# Qwiic_RTC_RV8803.net
KiCad netlist of a schematic drawn in EAGLE
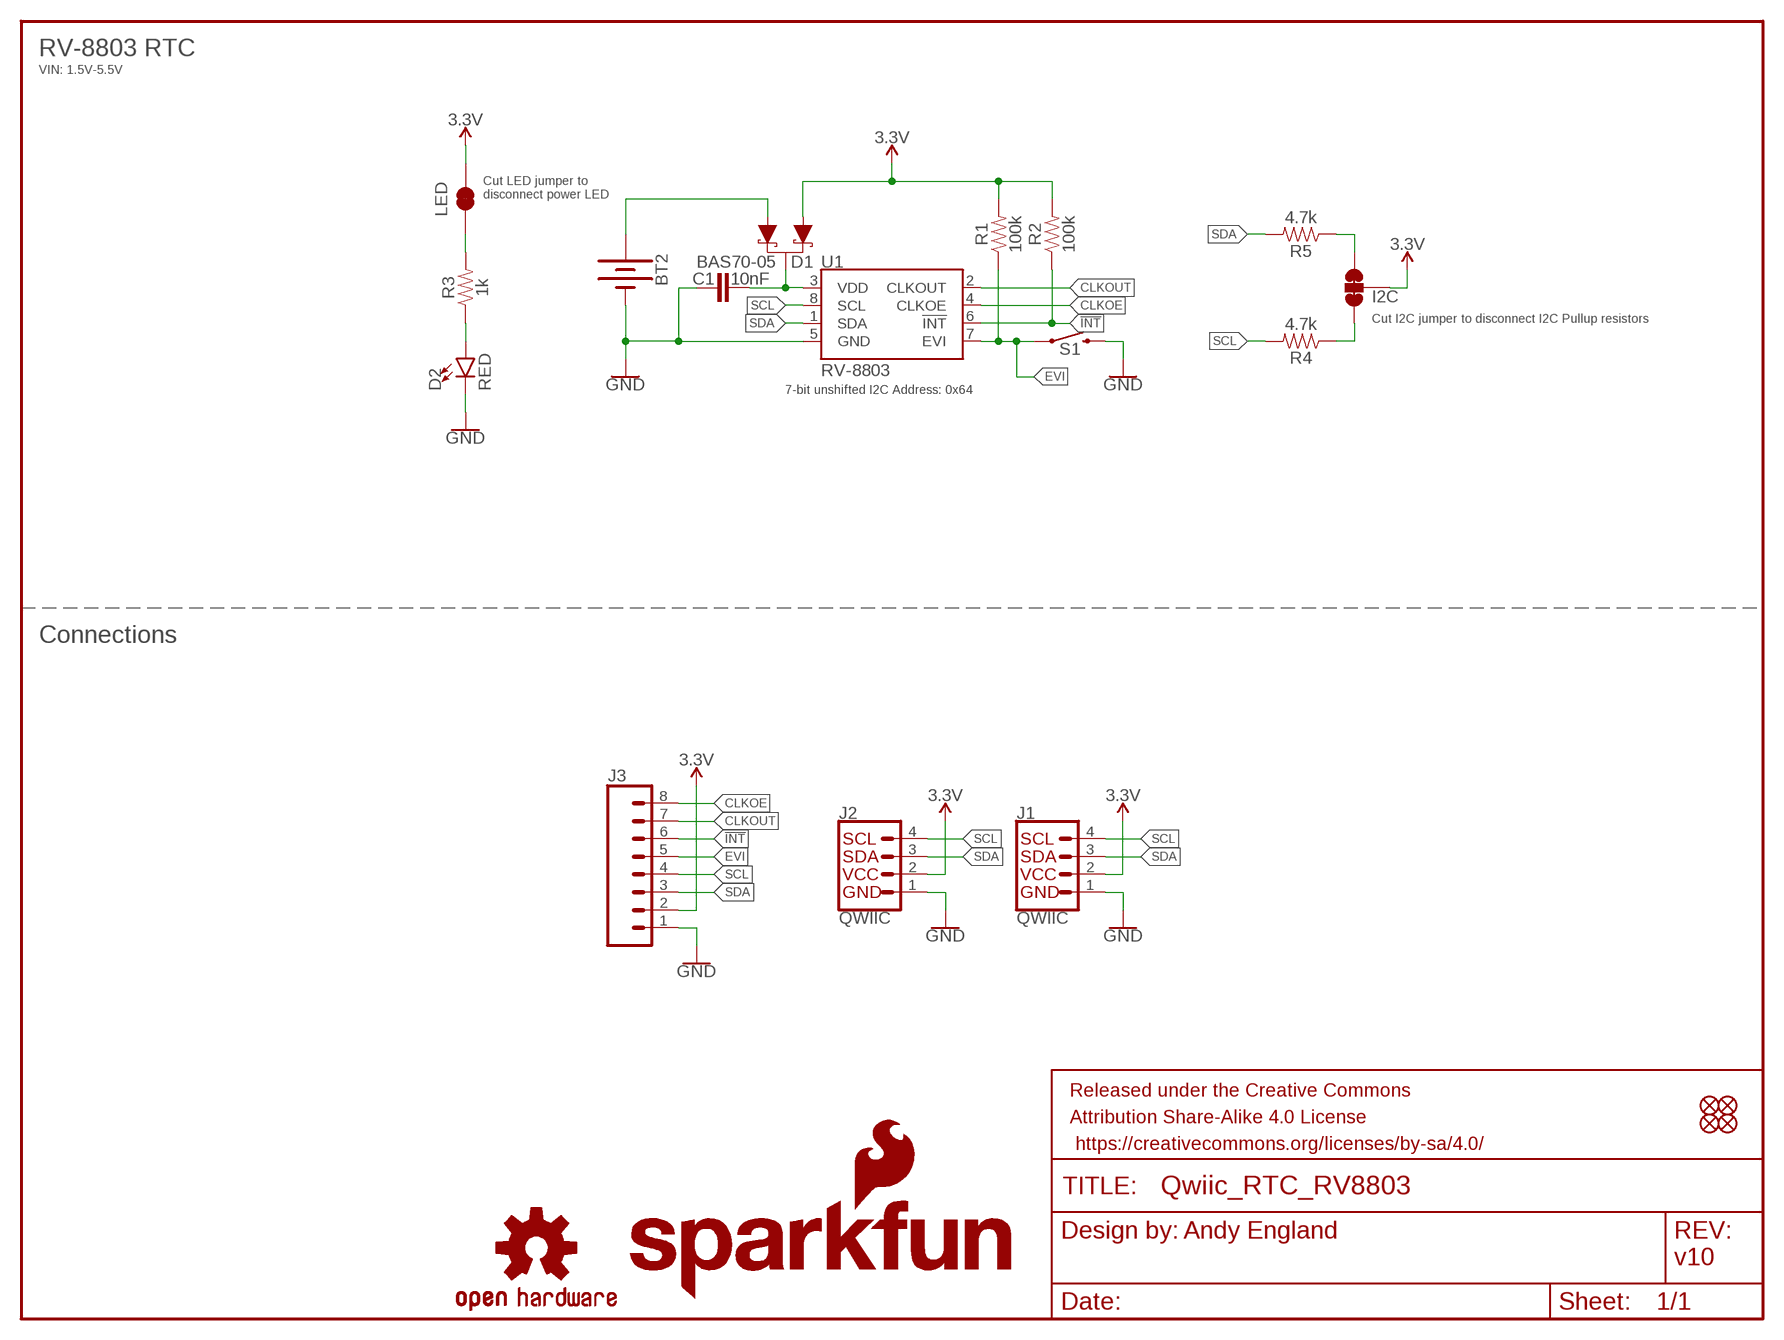
[diagram p0: schematic, sheet 1]

(export (version "E")
  (design (tool "Eeschema 10.0.6"))
  (components
    (comp (ref "BT2")
      (value "BATTERY-12MM_SMD")
      (footprint "eagle-import:BATTCON_12MM")
      (libsource (lib "eagle-import") (part "BATTERY-12MM_SMD"))
    )
    (comp (ref "C1")
      (value "10nF")
      (footprint "eagle-import:0603")
      (libsource (lib "eagle-import") (part "10NF-0603-50V-10%"))
    )
    (comp (ref "D1")
      (value "BAS70-05")
      (footprint "eagle-import:SOT23-3")
      (libsource (lib "eagle-import") (part "DIODE-SCHOTTKY-DUAL"))
    )
    (comp (ref "D2")
      (value "RED")
      (footprint "eagle-import:LED-0603")
      (libsource (lib "eagle-import") (part "LED-RED0603"))
    )
    (comp (ref "FD1")
      (value "FIDUCIALUFIDUCIAL")
      (footprint "eagle-import:FIDUCIAL-MICRO")
      (libsource (lib "eagle-import") (part "FIDUCIALUFIDUCIAL"))
    )
    (comp (ref "FD2")
      (value "FIDUCIALUFIDUCIAL")
      (footprint "eagle-import:FIDUCIAL-MICRO")
      (libsource (lib "eagle-import") (part "FIDUCIALUFIDUCIAL"))
    )
    (comp (ref "FD3")
      (value "FIDUCIALUFIDUCIAL")
      (footprint "eagle-import:FIDUCIAL-MICRO")
      (libsource (lib "eagle-import") (part "FIDUCIALUFIDUCIAL"))
    )
    (comp (ref "FD4")
      (value "FIDUCIALUFIDUCIAL")
      (footprint "eagle-import:FIDUCIAL-MICRO")
      (libsource (lib "eagle-import") (part "FIDUCIALUFIDUCIAL"))
    )
    (comp (ref "FRAME1")
      (value "FRAME-LETTER")
      (footprint "eagle-import:CREATIVE_COMMONS")
      (libsource (lib "eagle-import") (part "FRAME-LETTER"))
    )
    (comp (ref "I2C")
      (value "JUMPER-SMT_3_2-NC_TRACE_NO-SILK")
      (footprint "eagle-import:SMT-JUMPER_3_2-NC_TRACE_NO-SILK")
      (libsource (lib "eagle-import") (part "JUMPER-SMT_3_2-NC_TRACE_NO-SILK"))
    )
    (comp (ref "J1")
      (value "QWIIC")
      (footprint "eagle-import:JST04_1MM_RA")
      (libsource (lib "eagle-import") (part "QWIIC_CONNECTORJS-1MM"))
    )
    (comp (ref "J2")
      (value "QWIIC")
      (footprint "eagle-import:JST04_1MM_RA")
      (libsource (lib "eagle-import") (part "QWIIC_CONNECTORJS-1MM"))
    )
    (comp (ref "J3")
      (value "CONN_08NO_SILK_FEMALE_PTH")
      (footprint "eagle-import:1X08_NO_SILK")
      (libsource (lib "eagle-import") (part "CONN_08NO_SILK_FEMALE_PTH"))
    )
    (comp (ref "LED")
      (value "JUMPER-SMT_2_NC_TRACE_NO-SILK")
      (footprint "eagle-import:SMT-JUMPER_2_NC_TRACE_NO-SILK")
      (libsource (lib "eagle-import") (part "JUMPER-SMT_2_NC_TRACE_NO-SILK"))
    )
    (comp (ref "LOGO1")
      (value "SFE_LOGO_NAME_FLAME.1_INCH")
      (footprint "eagle-import:SFE_LOGO_NAME_FLAME_.1")
      (libsource (lib "eagle-import") (part "SFE_LOGO_NAME_FLAME.1_INCH"))
    )
    (comp (ref "LOGO2")
      (value "OSHW-LOGOS")
      (footprint "eagle-import:OSHW-LOGO-S")
      (libsource (lib "eagle-import") (part "OSHW-LOGOS"))
    )
    (comp (ref "LOGO3")
      (value "SFE_LOGO_FLAME.1_INCH")
      (footprint "eagle-import:SFE_LOGO_FLAME_.1")
      (libsource (lib "eagle-import") (part "SFE_LOGO_FLAME.1_INCH"))
    )
    (comp (ref "R1")
      (value "100k")
      (footprint "eagle-import:0603")
      (libsource (lib "eagle-import") (part "100KOHM-0603-1/10W-1%"))
    )
    (comp (ref "R2")
      (value "100k")
      (footprint "eagle-import:0603")
      (libsource (lib "eagle-import") (part "100KOHM-0603-1/10W-1%"))
    )
    (comp (ref "R3")
      (value "1k")
      (footprint "eagle-import:0603")
      (libsource (lib "eagle-import") (part "1KOHM-0603-1/10W-1%"))
    )
    (comp (ref "R4")
      (value "4.7k")
      (footprint "eagle-import:0603")
      (libsource (lib "eagle-import") (part "4.7KOHM-0603-1/10W-1%"))
    )
    (comp (ref "R5")
      (value "4.7k")
      (footprint "eagle-import:0603")
      (libsource (lib "eagle-import") (part "4.7KOHM-0603-1/10W-1%"))
    )
    (comp (ref "S1")
      (value "MOMENTARY-SWITCH-SPST-SMD-4.6X2.8MM")
      (footprint "eagle-import:TACTILE_SWITCH_SMD_4.6X2.8MM")
      (libsource (lib "eagle-import") (part "MOMENTARY-SWITCH-SPST-SMD-4.6X2.8MM"))
    )
    (comp (ref "U1")
      (value "RV-8803")
      (footprint "eagle-import:RV-3028")
      (libsource (lib "eagle-import") (part "RV-8803"))
    )
  )
  (nets
    (net (code "1") (name "/~{INT}") (class "Default")
      (node (ref "J3") (pin "6") (pinfunction "6_6") (pintype "passive"))
      (node (ref "R2") (pin "1") (pinfunction "1_1") (pintype "passive"))
      (node (ref "U1") (pin "6") (pinfunction "~{INT}_6") (pintype "bidirectional"))
    )
    (net (code "2") (name "3.3V") (class "Default")
      (node (ref "D1") (pin "1") (pinfunction "A_1") (pintype "passive"))
      (node (ref "I2C") (pin "2") (pinfunction "2_2") (pintype "passive"))
      (node (ref "J1") (pin "2") (pinfunction "2_2") (pintype "power_in"))
      (node (ref "J2") (pin "2") (pinfunction "2_2") (pintype "power_in"))
      (node (ref "J3") (pin "2") (pinfunction "2_2") (pintype "passive"))
      (node (ref "LED") (pin "2") (pinfunction "2_2") (pintype "passive"))
      (node (ref "R1") (pin "2") (pinfunction "2_2") (pintype "passive"))
      (node (ref "R2") (pin "2") (pinfunction "2_2") (pintype "passive"))
    )
    (net (code "3") (name "CLKOE") (class "Default")
      (node (ref "J3") (pin "8") (pinfunction "8_8") (pintype "passive"))
      (node (ref "U1") (pin "4") (pinfunction "CLKOE_4") (pintype "bidirectional"))
    )
    (net (code "4") (name "CLKOUT") (class "Default")
      (node (ref "J3") (pin "7") (pinfunction "7_7") (pintype "passive"))
      (node (ref "U1") (pin "2") (pinfunction "CLKOUT_2") (pintype "bidirectional"))
    )
    (net (code "5") (name "EVI") (class "Default")
      (node (ref "J3") (pin "5") (pinfunction "5_5") (pintype "passive"))
      (node (ref "R1") (pin "1") (pinfunction "1_1") (pintype "passive"))
      (node (ref "S1") (pin "1") (pinfunction "1_1") (pintype "passive"))
      (node (ref "S1") (pin "2") (pinfunction "1_2") (pintype "passive"))
      (node (ref "U1") (pin "7") (pinfunction "EVI_7") (pintype "bidirectional"))
    )
    (net (code "6") (name "GND") (class "Default")
      (node (ref "BT2") (pin "GND") (pinfunction "-_GND") (pintype "power_in"))
      (node (ref "C1") (pin "1") (pinfunction "1_1") (pintype "passive"))
      (node (ref "D2") (pin "C") (pinfunction "C_C") (pintype "passive"))
      (node (ref "J1") (pin "1") (pinfunction "1_1") (pintype "power_in"))
      (node (ref "J2") (pin "1") (pinfunction "1_1") (pintype "power_in"))
      (node (ref "J3") (pin "1") (pinfunction "1_1") (pintype "passive"))
      (node (ref "S1") (pin "3") (pinfunction "2_3") (pintype "passive"))
      (node (ref "S1") (pin "4") (pinfunction "2_4") (pintype "passive"))
      (node (ref "U1") (pin "5") (pinfunction "GND_5") (pintype "bidirectional"))
    )
    (net (code "7") (name "Net-(BT2-+)") (class "Default")
      (node (ref "BT2") (pin "PWR@1") (pinfunction "+_PWR@1") (pintype "power_in"))
      (node (ref "D1") (pin "2") (pinfunction "A1_2") (pintype "passive"))
    )
    (net (code "8") (name "Net-(D1-C)") (class "Default")
      (node (ref "C1") (pin "2") (pinfunction "2_2") (pintype "passive"))
      (node (ref "D1") (pin "3") (pinfunction "C_3") (pintype "passive"))
      (node (ref "U1") (pin "3") (pinfunction "VDD_3") (pintype "bidirectional"))
    )
    (net (code "9") (name "Net-(D2-PadA)") (class "Default")
      (node (ref "D2") (pin "A") (pinfunction "A_A") (pintype "passive"))
      (node (ref "R3") (pin "1") (pinfunction "1_1") (pintype "passive"))
    )
    (net (code "10") (name "Net-(I2C-Pad1)") (class "Default")
      (node (ref "I2C") (pin "1") (pinfunction "1_1") (pintype "passive"))
      (node (ref "R4") (pin "1") (pinfunction "1_1") (pintype "passive"))
    )
    (net (code "11") (name "Net-(I2C-Pad3)") (class "Default")
      (node (ref "I2C") (pin "3") (pinfunction "3_3") (pintype "passive"))
      (node (ref "R5") (pin "1") (pinfunction "1_1") (pintype "passive"))
    )
    (net (code "12") (name "Net-(LED-Pad1)") (class "Default")
      (node (ref "LED") (pin "1") (pinfunction "1_1") (pintype "passive"))
      (node (ref "R3") (pin "2") (pinfunction "2_2") (pintype "passive"))
    )
    (net (code "13") (name "SCL") (class "Default")
      (node (ref "J1") (pin "4") (pinfunction "4_4") (pintype "passive"))
      (node (ref "J2") (pin "4") (pinfunction "4_4") (pintype "passive"))
      (node (ref "J3") (pin "4") (pinfunction "4_4") (pintype "passive"))
      (node (ref "R4") (pin "2") (pinfunction "2_2") (pintype "passive"))
      (node (ref "U1") (pin "8") (pinfunction "SCL_8") (pintype "bidirectional"))
    )
    (net (code "14") (name "SDA") (class "Default")
      (node (ref "J1") (pin "3") (pinfunction "3_3") (pintype "passive"))
      (node (ref "J2") (pin "3") (pinfunction "3_3") (pintype "passive"))
      (node (ref "J3") (pin "3") (pinfunction "3_3") (pintype "passive"))
      (node (ref "R5") (pin "2") (pinfunction "2_2") (pintype "passive"))
      (node (ref "U1") (pin "1") (pinfunction "SDA_1") (pintype "bidirectional"))
    )
  )
)
